# Modulo_Generico.net
KiCad netlist of a schematic drawn in Altium Designer
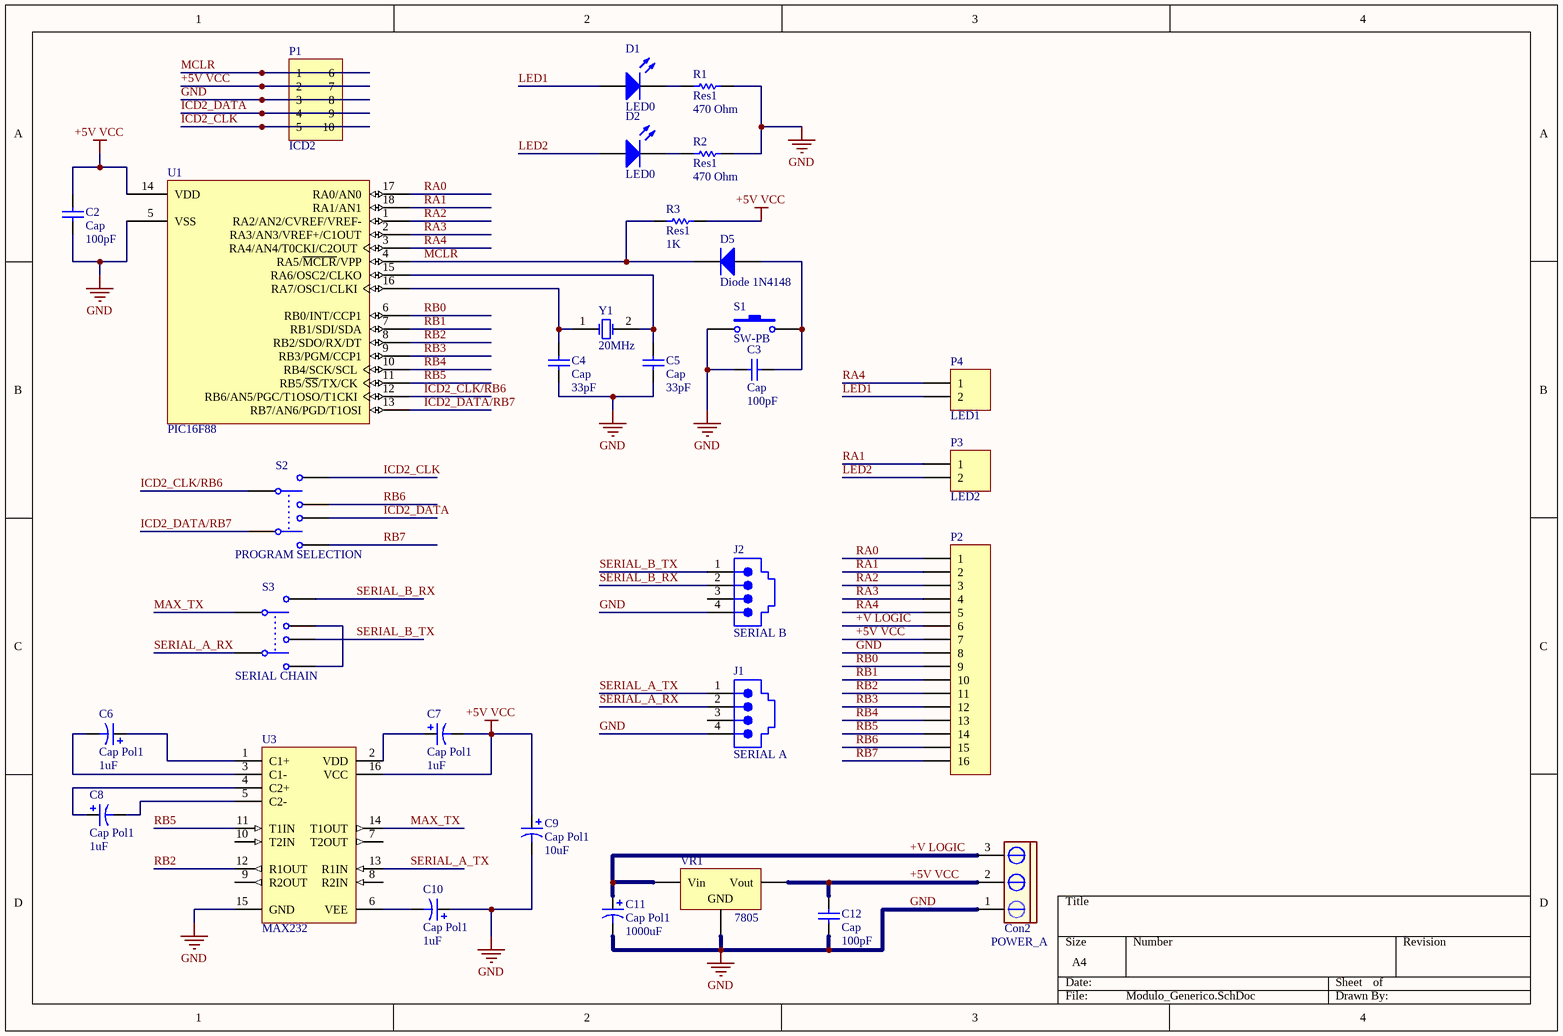
[diagram p0: Modulo_Generico.SchDoc]

(export (version "E")
  (design (tool "Eeschema 10.0.6"))
  (components
    (comp (ref "C2")
      (value "Cap")
      (footprint "CAPR2.54-5.1x3.2")
      (description "Capacitor")
      (fields (field (name "ALTIUM_VALUE") "100pF") (field (name "PUBLISHER") "Altium Limited"))
      (libsource (lib "Miscellaneous Devices") (part "Cap"))
    )
    (comp (ref "C3")
      (value "Cap")
      (footprint "CAPR2.54-5.1x3.2")
      (description "Capacitor")
      (fields (field (name "ALTIUM_VALUE") "100pF") (field (name "PUBLISHER") "Altium Limited"))
      (libsource (lib "Miscellaneous Devices") (part "Cap"))
    )
    (comp (ref "C4")
      (value "Cap")
      (footprint "CAPR2.54-5.1x3.2")
      (description "Capacitor")
      (fields (field (name "ALTIUM_VALUE") "33pF") (field (name "PUBLISHER") "Altium Limited"))
      (libsource (lib "Miscellaneous Devices") (part "Cap"))
    )
    (comp (ref "C5")
      (value "Cap")
      (footprint "CAPR2.54-5.1x3.2")
      (description "Capacitor")
      (fields (field (name "ALTIUM_VALUE") "33pF") (field (name "PUBLISHER") "Altium Limited"))
      (libsource (lib "Miscellaneous Devices") (part "Cap"))
    )
    (comp (ref "C6")
      (value "Cap Pol1")
      (footprint "CAPPR2-5x6.8")
      (description "Polarized Capacitor (Radial)")
      (fields (field (name "ALTIUM_VALUE") "1uF") (field (name "PUBLISHER") "Altium Limited"))
      (libsource (lib "Miscellaneous Devices") (part "Cap Pol1"))
    )
    (comp (ref "C7")
      (value "Cap Pol1")
      (footprint "CAPPR2-5x6.8")
      (description "Polarized Capacitor (Radial)")
      (fields (field (name "ALTIUM_VALUE") "1uF") (field (name "PUBLISHER") "Altium Limited"))
      (libsource (lib "Miscellaneous Devices") (part "Cap Pol1"))
    )
    (comp (ref "C8")
      (value "Cap Pol1")
      (footprint "CAPPR2-5x6.8")
      (description "Polarized Capacitor (Radial)")
      (fields (field (name "ALTIUM_VALUE") "1uF") (field (name "PUBLISHER") "Altium Limited"))
      (libsource (lib "Miscellaneous Devices") (part "Cap Pol1"))
    )
    (comp (ref "C9")
      (value "Cap Pol1")
      (footprint "CAPPR2-5x6.8")
      (description "Polarized Capacitor (Radial)")
      (fields (field (name "ALTIUM_VALUE") "10uF") (field (name "PUBLISHER") "Altium Limited"))
      (libsource (lib "Miscellaneous Devices") (part "Cap Pol1"))
    )
    (comp (ref "C10")
      (value "Cap Pol1")
      (footprint "CAPPR2-5x6.8")
      (description "Polarized Capacitor (Radial)")
      (fields (field (name "ALTIUM_VALUE") "1uF") (field (name "PUBLISHER") "Altium Limited"))
      (libsource (lib "Miscellaneous Devices") (part "Cap Pol1"))
    )
    (comp (ref "C11")
      (value "Cap Pol1")
      (footprint "RB5-10.5")
      (description "Polarized Capacitor (Radial)")
      (fields (field (name "ALTIUM_VALUE") "1000uF") (field (name "PUBLISHER") "Altium Limited"))
      (libsource (lib "Miscellaneous Devices") (part "Cap Pol1"))
    )
    (comp (ref "C12")
      (value "Cap")
      (footprint "CAPR2.54-5.1x3.2")
      (description "Capacitor")
      (fields (field (name "ALTIUM_VALUE") "100pF") (field (name "PUBLISHER") "Altium Limited"))
      (libsource (lib "Miscellaneous Devices") (part "Cap"))
    )
    (comp (ref "Con2")
      (value "POWER_A")
      (footprint "My_CN3")
      (description "Connector green screw")
      (libsource (lib "Protel_Library") (part "CON3 pin Green"))
    )
    (comp (ref "D1")
      (value "LED0")
      (footprint "LED-0")
      (description "Typical INFRARED GaAs LED")
      (fields (field (name "PUBLISHER") "Altium Limited"))
      (libsource (lib "Miscellaneous Devices") (part "LED0"))
    )
    (comp (ref "D2")
      (value "LED0")
      (footprint "LED-0")
      (description "Typical INFRARED GaAs LED")
      (fields (field (name "PUBLISHER") "Altium Limited"))
      (libsource (lib "Miscellaneous Devices") (part "LED0"))
    )
    (comp (ref "D5")
      (value "Diode 1N4148")
      (footprint "DIO7.1-3.9x1.9")
      (description "High Conductance Fast Diode")
      (fields (field (name "PUBLISHER") "Altium Limited"))
      (libsource (lib "Miscellaneous Devices") (part "Diode 1N4148"))
    )
    (comp (ref "J1")
      (value "SERIAL A")
      (footprint "15-43-6245")
      (description "Right Angle, Standard Profile, RJ45-Keyed, Flange Mount PCB Jack")
      (fields (field (name "PUBLISHER") "Altium Limited"))
      (libsource (lib "Molex Modular Jack Right Angle") (part "15-43-6245"))
    )
    (comp (ref "J2")
      (value "SERIAL B")
      (footprint "15-43-6245")
      (description "Right Angle, Standard Profile, RJ45-Keyed, Flange Mount PCB Jack")
      (fields (field (name "PUBLISHER") "Altium Limited"))
      (libsource (lib "Molex Modular Jack Right Angle") (part "15-43-6245"))
    )
    (comp (ref "P1")
      (value "ICD2")
      (footprint "HEADER10_5x2_B")
      (description "Header, 5-Pin, Dual row")
      (fields (field (name "PUBLISHER") "Altium Limited"))
      (libsource (lib "Miscellaneous Connectors") (part "Header 5X2A"))
    )
    (comp (ref "P2")
      (value "Header 16")
      (footprint "My_1X16")
      (description "Header, 16-Pin")
      (fields (field (name "PUBLISHER") "Altium Limited"))
      (libsource (lib "Protel_Library") (part "Header 16"))
    )
    (comp (ref "P3")
      (value "LED2")
      (footprint "HDR1X2")
      (description "Header, 2-Pin")
      (fields (field (name "PUBLISHER") "Altium Limited"))
      (libsource (lib "Miscellaneous Connectors") (part "Header 2"))
    )
    (comp (ref "P4")
      (value "LED1")
      (footprint "HDR1X2")
      (description "Header, 2-Pin")
      (fields (field (name "PUBLISHER") "Altium Limited"))
      (libsource (lib "Miscellaneous Connectors") (part "Header 2"))
    )
    (comp (ref "R1")
      (value "Res1")
      (footprint "AXIAL-0.3")
      (description "Resistor")
      (fields (field (name "ALTIUM_VALUE") "470 Ohm") (field (name "PUBLISHER") "Altium Limited"))
      (libsource (lib "Miscellaneous Devices") (part "Res1"))
    )
    (comp (ref "R2")
      (value "Res1")
      (footprint "AXIAL-0.3")
      (description "Resistor")
      (fields (field (name "ALTIUM_VALUE") "470 Ohm") (field (name "PUBLISHER") "Altium Limited"))
      (libsource (lib "Miscellaneous Devices") (part "Res1"))
    )
    (comp (ref "R3")
      (value "Res1")
      (footprint "AXIAL-0.3")
      (description "Resistor")
      (fields (field (name "ALTIUM_VALUE") "1K") (field (name "PUBLISHER") "Altium Limited"))
      (libsource (lib "Miscellaneous Devices") (part "Res1"))
    )
    (comp (ref "S1")
      (value "SW-PB")
      (footprint "TS-063")
      (description "Switch")
      (fields (field (name "PUBLISHER") "Altium Limited"))
      (libsource (lib "Miscellaneous Devices") (part "SW-PB"))
    )
    (comp (ref "S2")
      (value "PROGRAM SELECTION")
      (footprint "LD-202mini")
      (description "Double-Pole, Double-Throw Switch")
      (fields (field (name "PUBLISHER") "Altium Limited"))
      (libsource (lib "Miscellaneous Devices") (part "SW-DPDT"))
    )
    (comp (ref "S3")
      (value "SERIAL CHAIN")
      (footprint "LD-202mini")
      (description "Double-Pole, Double-Throw Switch")
      (fields (field (name "PUBLISHER") "Altium Limited"))
      (libsource (lib "Miscellaneous Devices") (part "SW-DPDT"))
    )
    (comp (ref "U1")
      (value "PIC16F88")
      (footprint "PDIP300-P18")
      (fields (field (name "PUBLISHER") "Altium Limited"))
      (libsource (lib "Microchip Microcontroller 8-Bit PIC16") (part "PIC16F88-E/P"))
    )
    (comp (ref "U3")
      (value "MAX232")
      (footprint "PE16A")
      (description "+5V Powered, Multi-Channel RS-232 Driver/Receiver")
      (fields (field (name "PUBLISHER") "Altium Limited"))
      (libsource (lib "Maxim Communication Transceiver") (part "MAX232ACPE"))
    )
    (comp (ref "VR1")
      (value "7805")
      (footprint "My_TO-220")
      (description "Voltage Regulator")
      (fields (field (name "PUBLISHER") "Altium Limited"))
      (libsource (lib "Miscellaneous Devices") (part "Volt Reg"))
    )
    (comp (ref "Y1")
      (value "20MHz")
      (footprint "My_Crystal")
      (description "Crystal Oscillator")
      (fields (field (name "PUBLISHER") "Altium Limited"))
      (libsource (lib "Miscellaneous Devices") (part "XTAL"))
    )
  )
  (nets
    (net (code "1") (name "+5V VCC") (class "Default")
      (node (ref "C12") (pin "2") (pinfunction "2_2") (pintype "passive"))
      (node (ref "C2") (pin "2") (pinfunction "2_2") (pintype "passive"))
      (node (ref "C7") (pin "2") (pinfunction "2_2") (pintype "passive"))
      (node (ref "C9") (pin "1") (pinfunction "1_1") (pintype "passive"))
      (node (ref "Con2") (pin "2") (pinfunction "2_2") (pintype "passive"))
      (node (ref "P1") (pin "2") (pinfunction "2_2") (pintype "passive"))
      (node (ref "P1") (pin "7") (pinfunction "7_7") (pintype "passive"))
      (node (ref "P2") (pin "7") (pinfunction "7_7") (pintype "passive"))
      (node (ref "R3") (pin "2") (pinfunction "2_2") (pintype "passive"))
      (node (ref "U1") (pin "14") (pinfunction "VDD_14") (pintype "power_in"))
      (node (ref "U3") (pin "16") (pinfunction "VCC_16") (pintype "power_in"))
      (node (ref "VR1") (pin "3") (pinfunction "Vout_3") (pintype "passive"))
    )
    (net (code "2") (name "/+V LOGIC") (class "Default")
      (node (ref "C11") (pin "1") (pinfunction "1_1") (pintype "passive"))
      (node (ref "Con2") (pin "3") (pinfunction "3_3") (pintype "passive"))
      (node (ref "P2") (pin "6") (pinfunction "6_6") (pintype "passive"))
      (node (ref "VR1") (pin "1") (pinfunction "Vin_1") (pintype "passive"))
    )
    (net (code "3") (name "/ICD2_CLK") (class "Default")
      (node (ref "P1") (pin "10") (pinfunction "10_10") (pintype "passive"))
      (node (ref "P1") (pin "5") (pinfunction "5_5") (pintype "passive"))
      (node (ref "S2") (pin "2") (pinfunction "2_2") (pintype "passive"))
    )
    (net (code "4") (name "/ICD2_CLK{slash}RB6") (class "Default")
      (node (ref "S2") (pin "1") (pinfunction "1_1") (pintype "passive"))
      (node (ref "U1") (pin "12") (pinfunction "RB6/AN5/PGC/T1OSO/T1CKI_12") (pintype "bidirectional"))
    )
    (net (code "5") (name "/ICD2_DATA") (class "Default")
      (node (ref "P1") (pin "4") (pinfunction "4_4") (pintype "passive"))
      (node (ref "P1") (pin "9") (pinfunction "9_9") (pintype "passive"))
      (node (ref "S2") (pin "5") (pinfunction "5_5") (pintype "passive"))
    )
    (net (code "6") (name "/ICD2_DATA{slash}RB7") (class "Default")
      (node (ref "S2") (pin "4") (pinfunction "4_4") (pintype "passive"))
      (node (ref "U1") (pin "13") (pinfunction "RB7/AN6/PGD/T1OSI_13") (pintype "bidirectional"))
    )
    (net (code "7") (name "/LED1") (class "Default")
      (node (ref "D1") (pin "1") (pinfunction "A_1") (pintype "passive"))
      (node (ref "P4") (pin "2") (pinfunction "2_2") (pintype "passive"))
    )
    (net (code "8") (name "/LED2") (class "Default")
      (node (ref "D2") (pin "1") (pinfunction "A_1") (pintype "passive"))
      (node (ref "P3") (pin "2") (pinfunction "2_2") (pintype "passive"))
    )
    (net (code "9") (name "/MAX_TX") (class "Default")
      (node (ref "S3") (pin "1") (pinfunction "1_1") (pintype "passive"))
      (node (ref "U3") (pin "14") (pinfunction "T1OUT_14") (pintype "output"))
    )
    (net (code "10") (name "/MCLR") (class "Default")
      (node (ref "D5") (pin "2") (pinfunction "K_2") (pintype "passive"))
      (node (ref "P1") (pin "1") (pinfunction "1_1") (pintype "passive"))
      (node (ref "P1") (pin "6") (pinfunction "6_6") (pintype "passive"))
      (node (ref "R3") (pin "1") (pinfunction "1_1") (pintype "passive"))
      (node (ref "U1") (pin "4") (pinfunction "RA5/~{MCLR}/VPP_4") (pintype "bidirectional"))
    )
    (net (code "11") (name "/RA0") (class "Default")
      (node (ref "P2") (pin "1") (pinfunction "1_1") (pintype "passive"))
      (node (ref "U1") (pin "17") (pinfunction "RA0/AN0_17") (pintype "bidirectional"))
    )
    (net (code "12") (name "/RA1") (class "Default")
      (node (ref "P2") (pin "2") (pinfunction "2_2") (pintype "passive"))
      (node (ref "P3") (pin "1") (pinfunction "1_1") (pintype "passive"))
      (node (ref "U1") (pin "18") (pinfunction "RA1/AN1_18") (pintype "bidirectional"))
    )
    (net (code "13") (name "/RA2") (class "Default")
      (node (ref "P2") (pin "3") (pinfunction "3_3") (pintype "passive"))
      (node (ref "U1") (pin "1") (pinfunction "RA2/AN2/CVREF/VREF-_1") (pintype "bidirectional"))
    )
    (net (code "14") (name "/RA3") (class "Default")
      (node (ref "P2") (pin "4") (pinfunction "4_4") (pintype "passive"))
      (node (ref "U1") (pin "2") (pinfunction "RA3/AN3/VREF+/C1OUT_2") (pintype "bidirectional"))
    )
    (net (code "15") (name "/RA4") (class "Default")
      (node (ref "P2") (pin "5") (pinfunction "5_5") (pintype "passive"))
      (node (ref "P4") (pin "1") (pinfunction "1_1") (pintype "passive"))
      (node (ref "U1") (pin "3") (pinfunction "RA4/AN4/T0CKI/C2OUT_3") (pintype "bidirectional"))
    )
    (net (code "16") (name "/RB0") (class "Default")
      (node (ref "P2") (pin "9") (pinfunction "9_9") (pintype "passive"))
      (node (ref "U1") (pin "6") (pinfunction "RB0/INT/CCP1_6") (pintype "bidirectional"))
    )
    (net (code "17") (name "/RB1") (class "Default")
      (node (ref "P2") (pin "10") (pinfunction "10_10") (pintype "passive"))
      (node (ref "U1") (pin "7") (pinfunction "RB1/SDI/SDA_7") (pintype "bidirectional"))
    )
    (net (code "18") (name "/RB2") (class "Default")
      (node (ref "P2") (pin "11") (pinfunction "11_11") (pintype "passive"))
      (node (ref "U1") (pin "8") (pinfunction "RB2/SDO/RX/DT_8") (pintype "bidirectional"))
      (node (ref "U3") (pin "12") (pinfunction "R1OUT_12") (pintype "output"))
    )
    (net (code "19") (name "/RB3") (class "Default")
      (node (ref "P2") (pin "12") (pinfunction "12_12") (pintype "passive"))
      (node (ref "U1") (pin "9") (pinfunction "RB3/PGM/CCP1_9") (pintype "bidirectional"))
    )
    (net (code "20") (name "/RB4") (class "Default")
      (node (ref "P2") (pin "13") (pinfunction "13_13") (pintype "passive"))
      (node (ref "U1") (pin "10") (pinfunction "RB4/SCK/SCL_10") (pintype "bidirectional"))
    )
    (net (code "21") (name "/RB5") (class "Default")
      (node (ref "P2") (pin "14") (pinfunction "14_14") (pintype "passive"))
      (node (ref "U1") (pin "11") (pinfunction "RB5/~{SS}/TX/CK_11") (pintype "bidirectional"))
      (node (ref "U3") (pin "11") (pinfunction "T1IN_11") (pintype "input"))
    )
    (net (code "22") (name "/RB6") (class "Default")
      (node (ref "P2") (pin "15") (pinfunction "15_15") (pintype "passive"))
      (node (ref "S2") (pin "3") (pinfunction "3_3") (pintype "passive"))
    )
    (net (code "23") (name "/RB7") (class "Default")
      (node (ref "P2") (pin "16") (pinfunction "16_16") (pintype "passive"))
      (node (ref "S2") (pin "6") (pinfunction "6_6") (pintype "passive"))
    )
    (net (code "24") (name "/SERIAL_A_RX") (class "Default")
      (node (ref "J1") (pin "2") (pinfunction "2_2") (pintype "passive"))
      (node (ref "S3") (pin "4") (pinfunction "4_4") (pintype "passive"))
    )
    (net (code "25") (name "/SERIAL_A_TX") (class "Default")
      (node (ref "J1") (pin "1") (pinfunction "1_1") (pintype "passive"))
      (node (ref "U3") (pin "13") (pinfunction "R1IN_13") (pintype "input"))
    )
    (net (code "26") (name "/SERIAL_B_RX") (class "Default")
      (node (ref "J2") (pin "2") (pinfunction "2_2") (pintype "passive"))
      (node (ref "S3") (pin "2") (pinfunction "2_2") (pintype "passive"))
    )
    (net (code "27") (name "/SERIAL_B_TX") (class "Default")
      (node (ref "J2") (pin "1") (pinfunction "1_1") (pintype "passive"))
      (node (ref "S3") (pin "5") (pinfunction "5_5") (pintype "passive"))
    )
    (net (code "28") (name "GND") (class "Default")
      (node (ref "C10") (pin "1") (pinfunction "1_1") (pintype "passive"))
      (node (ref "C11") (pin "2") (pinfunction "2_2") (pintype "passive"))
      (node (ref "C12") (pin "1") (pinfunction "1_1") (pintype "passive"))
      (node (ref "C2") (pin "1") (pinfunction "1_1") (pintype "passive"))
      (node (ref "C3") (pin "1") (pinfunction "1_1") (pintype "passive"))
      (node (ref "C4") (pin "1") (pinfunction "1_1") (pintype "passive"))
      (node (ref "C5") (pin "1") (pinfunction "1_1") (pintype "passive"))
      (node (ref "C9") (pin "2") (pinfunction "2_2") (pintype "passive"))
      (node (ref "Con2") (pin "1") (pinfunction "1_1") (pintype "passive"))
      (node (ref "J1") (pin "4") (pinfunction "4_4") (pintype "passive"))
      (node (ref "J2") (pin "4") (pinfunction "4_4") (pintype "passive"))
      (node (ref "P1") (pin "3") (pinfunction "3_3") (pintype "passive"))
      (node (ref "P1") (pin "8") (pinfunction "8_8") (pintype "passive"))
      (node (ref "P2") (pin "8") (pinfunction "8_8") (pintype "passive"))
      (node (ref "R1") (pin "2") (pinfunction "2_2") (pintype "passive"))
      (node (ref "R2") (pin "2") (pinfunction "2_2") (pintype "passive"))
      (node (ref "S1") (pin "1") (pinfunction "1_1") (pintype "passive"))
      (node (ref "U1") (pin "5") (pinfunction "VSS_5") (pintype "power_in"))
      (node (ref "U3") (pin "15") (pinfunction "GND_15") (pintype "power_in"))
      (node (ref "VR1") (pin "2") (pinfunction "GND_2") (pintype "passive"))
    )
    (net (code "29") (name "Net-(D1-K)") (class "Default")
      (node (ref "D1") (pin "2") (pinfunction "K_2") (pintype "passive"))
      (node (ref "R1") (pin "1") (pinfunction "1_1") (pintype "passive"))
    )
    (net (code "30") (name "Net-(D2-K)") (class "Default")
      (node (ref "D2") (pin "2") (pinfunction "K_2") (pintype "passive"))
      (node (ref "R2") (pin "1") (pinfunction "1_1") (pintype "passive"))
    )
    (net (code "31") (name "Net-(D5-A)") (class "Default")
      (node (ref "C3") (pin "2") (pinfunction "2_2") (pintype "passive"))
      (node (ref "D5") (pin "1") (pinfunction "A_1") (pintype "passive"))
      (node (ref "S1") (pin "2") (pinfunction "2_2") (pintype "passive"))
    )
    (net (code "32") (name "Net-(S3-Pad3)") (class "Default")
      (node (ref "S3") (pin "3") (pinfunction "3_3") (pintype "passive"))
      (node (ref "S3") (pin "6") (pinfunction "6_6") (pintype "passive"))
    )
    (net (code "33") (name "Net-(U1-RA6{slash}OSC2{slash}CLKO)") (class "Default")
      (node (ref "C5") (pin "2") (pinfunction "2_2") (pintype "passive"))
      (node (ref "U1") (pin "15") (pinfunction "RA6/OSC2/CLKO_15") (pintype "bidirectional"))
      (node (ref "Y1") (pin "2") (pinfunction "OSC2_2") (pintype "passive"))
    )
    (net (code "34") (name "Net-(U1-RA7{slash}OSC1{slash}CLKI)") (class "Default")
      (node (ref "C4") (pin "2") (pinfunction "2_2") (pintype "passive"))
      (node (ref "U1") (pin "16") (pinfunction "RA7/OSC1/CLKI_16") (pintype "bidirectional"))
      (node (ref "Y1") (pin "1") (pinfunction "OSC1_1") (pintype "passive"))
    )
    (net (code "35") (name "Net-(U3-C1+)") (class "Default")
      (node (ref "C6") (pin "1") (pinfunction "1_1") (pintype "passive"))
      (node (ref "U3") (pin "1") (pinfunction "C1+_1") (pintype "passive"))
    )
    (net (code "36") (name "Net-(U3-C1-)") (class "Default")
      (node (ref "C6") (pin "2") (pinfunction "2_2") (pintype "passive"))
      (node (ref "U3") (pin "3") (pinfunction "C1-_3") (pintype "passive"))
    )
    (net (code "37") (name "Net-(U3-C2+)") (class "Default")
      (node (ref "C8") (pin "1") (pinfunction "1_1") (pintype "passive"))
      (node (ref "U3") (pin "4") (pinfunction "C2+_4") (pintype "passive"))
    )
    (net (code "38") (name "Net-(U3-C2-)") (class "Default")
      (node (ref "C8") (pin "2") (pinfunction "2_2") (pintype "passive"))
      (node (ref "U3") (pin "5") (pinfunction "C2-_5") (pintype "passive"))
    )
    (net (code "39") (name "Net-(U3-VDD)") (class "Default")
      (node (ref "C7") (pin "1") (pinfunction "1_1") (pintype "passive"))
      (node (ref "U3") (pin "2") (pinfunction "VDD_2") (pintype "power_in"))
    )
    (net (code "40") (name "Net-(U3-VEE)") (class "Default")
      (node (ref "C10") (pin "2") (pinfunction "2_2") (pintype "passive"))
      (node (ref "U3") (pin "6") (pinfunction "VEE_6") (pintype "power_in"))
    )
    (net (code "41") (name "unconnected-(J1-Pad3)") (class "Default")
      (node (ref "J1") (pin "3") (pinfunction "3_3") (pintype "passive"))
    )
    (net (code "42") (name "unconnected-(J2-Pad3)") (class "Default")
      (node (ref "J2") (pin "3") (pinfunction "3_3") (pintype "passive"))
    )
    (net (code "43") (name "unconnected-(U3-R2IN-Pad8)") (class "Default")
      (node (ref "U3") (pin "8") (pinfunction "R2IN_8") (pintype "input"))
    )
    (net (code "44") (name "unconnected-(U3-R2OUT-Pad9)") (class "Default")
      (node (ref "U3") (pin "9") (pinfunction "R2OUT_9") (pintype "output"))
    )
    (net (code "45") (name "unconnected-(U3-T2IN-Pad10)") (class "Default")
      (node (ref "U3") (pin "10") (pinfunction "T2IN_10") (pintype "input"))
    )
    (net (code "46") (name "unconnected-(U3-T2OUT-Pad7)") (class "Default")
      (node (ref "U3") (pin "7") (pinfunction "T2OUT_7") (pintype "output"))
    )
  )
)
